# POWER.net
KiCad netlist of a schematic drawn in Altium Designer
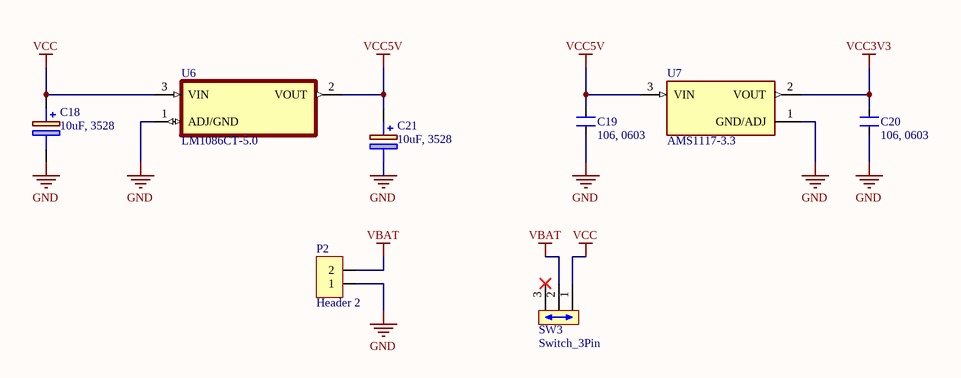
[diagram p0: POWER.SchDoc]

(export (version "E")
  (design (tool "Eeschema 10.0.6"))
  (components
    (comp (ref "C18")
      (value "10uF, 3528")
      (footprint "CAP-TANTAL-3528")
      (description "Tantalum Capacitor")
      (libsource (lib "LIB_Project2") (part "CAP Tantalum"))
    )
    (comp (ref "C19")
      (value "106, 0603")
      (footprint "SM-0603")
      (description "Cap SMD")
      (libsource (lib "KhanhBK_Library_4") (part "CM"))
    )
    (comp (ref "C20")
      (value "106, 0603")
      (footprint "SM-0603")
      (description "Cap SMD")
      (libsource (lib "KhanhBK_Library_4") (part "CM"))
    )
    (comp (ref "C21")
      (value "10uF, 3528")
      (footprint "CAP-TANTAL-3528")
      (description "Tantalum Capacitor")
      (libsource (lib "LIB_Project2") (part "CAP Tantalum"))
    )
    (comp (ref "P2")
      (value "Header 2")
      (footprint "HDR/Header/2")
      (description "Header, 2-Pin")
      (libsource (lib "connectors") (part "Header 2"))
    )
    (comp (ref "SW3")
      (value "Switch_3Pin")
      (footprint "SW-12F23")
      (description "Switch")
      (fields (field (name "PUBLISHER") "Altium Limited"))
      (libsource (lib "KhanhBK_SCH_Lib_5") (part "Switch_3Pin"))
    )
    (comp (ref "U6")
      (value "LM1086CT-5.0")
      (footprint "TO254P1054X470X1955-3")
      (fields
        (field (name "MF") "{'manufacturer': u'Texas Instruments'}")
        (field (name "MP") "LM1086CT-5.0/NOPB")
      )
      (libsource (lib "SnapEDA_Library") (part "LM1086CT-5.0"))
    )
    (comp (ref "U7")
      (value "AMS1117-3.3")
      (footprint "SOT229P700X180-4N")
      (fields (field (name "MF") "{'manufacturer': u'Advanced Monolithic Systems'}"))
      (libsource (lib "SnapEDA_Library") (part "AMS1117-3.3"))
    )
  )
  (nets
    (net (code "1") (name "GND") (class "Default")
      (node (ref "C18") (pin "2") (pinfunction "2_2") (pintype "passive"))
      (node (ref "C19") (pin "1") (pinfunction "1_1") (pintype "passive"))
      (node (ref "C20") (pin "1") (pinfunction "1_1") (pintype "passive"))
      (node (ref "C21") (pin "2") (pinfunction "2_2") (pintype "passive"))
      (node (ref "P2") (pin "1") (pinfunction "1_1") (pintype "passive"))
      (node (ref "U6") (pin "1") (pinfunction "ADJ/GND_1") (pintype "bidirectional"))
      (node (ref "U7") (pin "1") (pinfunction "GND/ADJ_1") (pintype "power_in"))
    )
    (net (code "2") (name "VBAT") (class "Default")
      (node (ref "P2") (pin "2") (pinfunction "2_2") (pintype "passive"))
      (node (ref "SW3") (pin "2") (pinfunction "COMMON_2") (pintype "passive"))
    )
    (net (code "3") (name "VCC") (class "Default")
      (node (ref "C18") (pin "1") (pinfunction "1_1") (pintype "passive"))
      (node (ref "SW3") (pin "1") (pinfunction "1_1") (pintype "passive"))
      (node (ref "U6") (pin "3") (pinfunction "VIN_3") (pintype "input"))
    )
    (net (code "4") (name "VCC3V3") (class "Default")
      (node (ref "C20") (pin "2") (pinfunction "2_2") (pintype "passive"))
      (node (ref "U7") (pin "2") (pinfunction "VOUT_2") (pintype "output"))
    )
    (net (code "5") (name "VCC5V") (class "Default")
      (node (ref "C19") (pin "2") (pinfunction "2_2") (pintype "passive"))
      (node (ref "C21") (pin "1") (pinfunction "1_1") (pintype "passive"))
      (node (ref "U6") (pin "2") (pinfunction "VOUT_2") (pintype "output"))
      (node (ref "U7") (pin "3") (pinfunction "VIN_3") (pintype "input"))
    )
    (net (code "6") (name "unconnected-(SW3-Pad3)") (class "Default")
      (node (ref "SW3") (pin "3") (pinfunction "3_3") (pintype "passive+no_connect"))
    )
  )
)
